# Sallen_key_LPF.net
KiCad netlist of a schematic drawn in Altium Designer
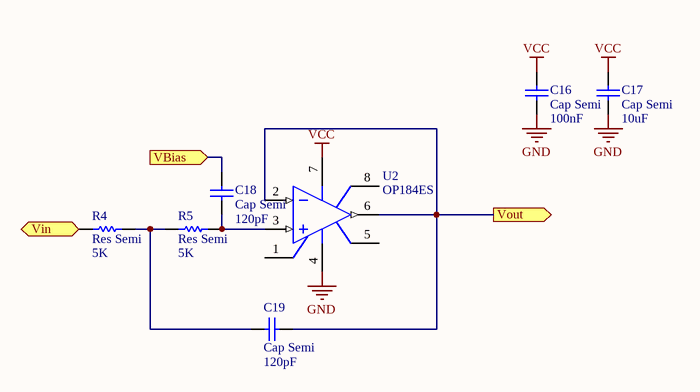
[diagram p0: Sallen_key_LPF.SchDoc]

(export (version "E")
  (design (tool "Eeschema 10.0.6"))
  (components
    (comp (ref "C16")
      (value "Cap Semi")
      (footprint "C0805")
      (description "Capacitor (Semiconductor SIM Model)")
      (fields (field (name "ALTIUM_VALUE") "100nF") (field (name "PUBLISHER") "Altium Limited"))
      (libsource (lib "Miscellaneous Devices") (part "Cap Semi"))
    )
    (comp (ref "C17")
      (value "Cap Semi")
      (footprint "C0805")
      (description "Capacitor (Semiconductor SIM Model)")
      (fields (field (name "ALTIUM_VALUE") "10uF") (field (name "PUBLISHER") "Altium Limited"))
      (libsource (lib "Miscellaneous Devices") (part "Cap Semi"))
    )
    (comp (ref "C18")
      (value "Cap Semi")
      (footprint "C0805")
      (description "Capacitor (Semiconductor SIM Model)")
      (fields (field (name "ALTIUM_VALUE") "120pF") (field (name "PUBLISHER") "Altium Limited"))
      (libsource (lib "Miscellaneous Devices") (part "Cap Semi"))
    )
    (comp (ref "C19")
      (value "Cap Semi")
      (footprint "C0805")
      (description "Capacitor (Semiconductor SIM Model)")
      (fields (field (name "ALTIUM_VALUE") "120pF") (field (name "PUBLISHER") "Altium Limited"))
      (libsource (lib "Miscellaneous Devices") (part "Cap Semi"))
    )
    (comp (ref "R4")
      (value "Res Semi")
      (footprint "6-0805_M")
      (description "Semiconductor Resistor")
      (fields (field (name "ALTIUM_VALUE") "5K") (field (name "PUBLISHER") "Altium Limited"))
      (libsource (lib "Miscellaneous Devices") (part "Res Semi"))
    )
    (comp (ref "R5")
      (value "Res Semi")
      (footprint "6-0805_M")
      (description "Semiconductor Resistor")
      (fields (field (name "ALTIUM_VALUE") "5K") (field (name "PUBLISHER") "Altium Limited"))
      (libsource (lib "Miscellaneous Devices") (part "Res Semi"))
    )
    (comp (ref "U2")
      (value "OP184ES")
      (footprint "SO-8")
      (description "Precision Rail-to-Rail Input and Ouput Operational Amplifier")
      (fields (field (name "PUBLISHER") "Altium Limited"))
      (libsource (lib "AD Operational Amplifier") (part "OP184ES"))
    )
  )
  (nets
    (net (code "1") (name "/VBias") (class "Default")
      (node (ref "C18") (pin "2") (pinfunction "2_2") (pintype "passive"))
    )
    (net (code "2") (name "/Vin") (class "Default")
      (node (ref "R4") (pin "1") (pinfunction "1_1") (pintype "passive"))
    )
    (net (code "3") (name "/Vout") (class "Default")
      (node (ref "C19") (pin "1") (pinfunction "1_1") (pintype "passive"))
      (node (ref "U2") (pin "2") (pinfunction "IN-_2") (pintype "input"))
      (node (ref "U2") (pin "6") (pinfunction "OUT_6") (pintype "output"))
    )
    (net (code "4") (name "GND") (class "Default")
      (node (ref "C16") (pin "1") (pinfunction "1_1") (pintype "passive"))
      (node (ref "C17") (pin "1") (pinfunction "1_1") (pintype "passive"))
      (node (ref "U2") (pin "4") (pinfunction "V-_4") (pintype "power_in"))
    )
    (net (code "5") (name "Net-(C19-Pad2)") (class "Default")
      (node (ref "C19") (pin "2") (pinfunction "2_2") (pintype "passive"))
      (node (ref "R4") (pin "2") (pinfunction "2_2") (pintype "passive"))
      (node (ref "R5") (pin "1") (pinfunction "1_1") (pintype "passive"))
    )
    (net (code "6") (name "Net-(U2-IN+)") (class "Default")
      (node (ref "C18") (pin "1") (pinfunction "1_1") (pintype "passive"))
      (node (ref "R5") (pin "2") (pinfunction "2_2") (pintype "passive"))
      (node (ref "U2") (pin "3") (pinfunction "IN+_3") (pintype "input"))
    )
    (net (code "7") (name "VCC") (class "Default")
      (node (ref "C16") (pin "2") (pinfunction "2_2") (pintype "passive"))
      (node (ref "C17") (pin "2") (pinfunction "2_2") (pintype "passive"))
      (node (ref "U2") (pin "7") (pinfunction "V+_7") (pintype "power_in"))
    )
    (net (code "8") (name "unconnected-(U2-NC-Pad8)") (class "Default")
      (node (ref "U2") (pin "8") (pinfunction "NC_8") (pintype "passive"))
    )
    (net (code "9") (name "unconnected-(U2-NUL-Pad1)") (class "Default")
      (node (ref "U2") (pin "1") (pinfunction "NUL_1") (pintype "passive"))
    )
    (net (code "10") (name "unconnected-(U2-NUL-Pad5)") (class "Default")
      (node (ref "U2") (pin "5") (pinfunction "NUL_5") (pintype "passive"))
    )
  )
)
